# Schematic.net
KiCad netlist of a schematic drawn in EAGLE
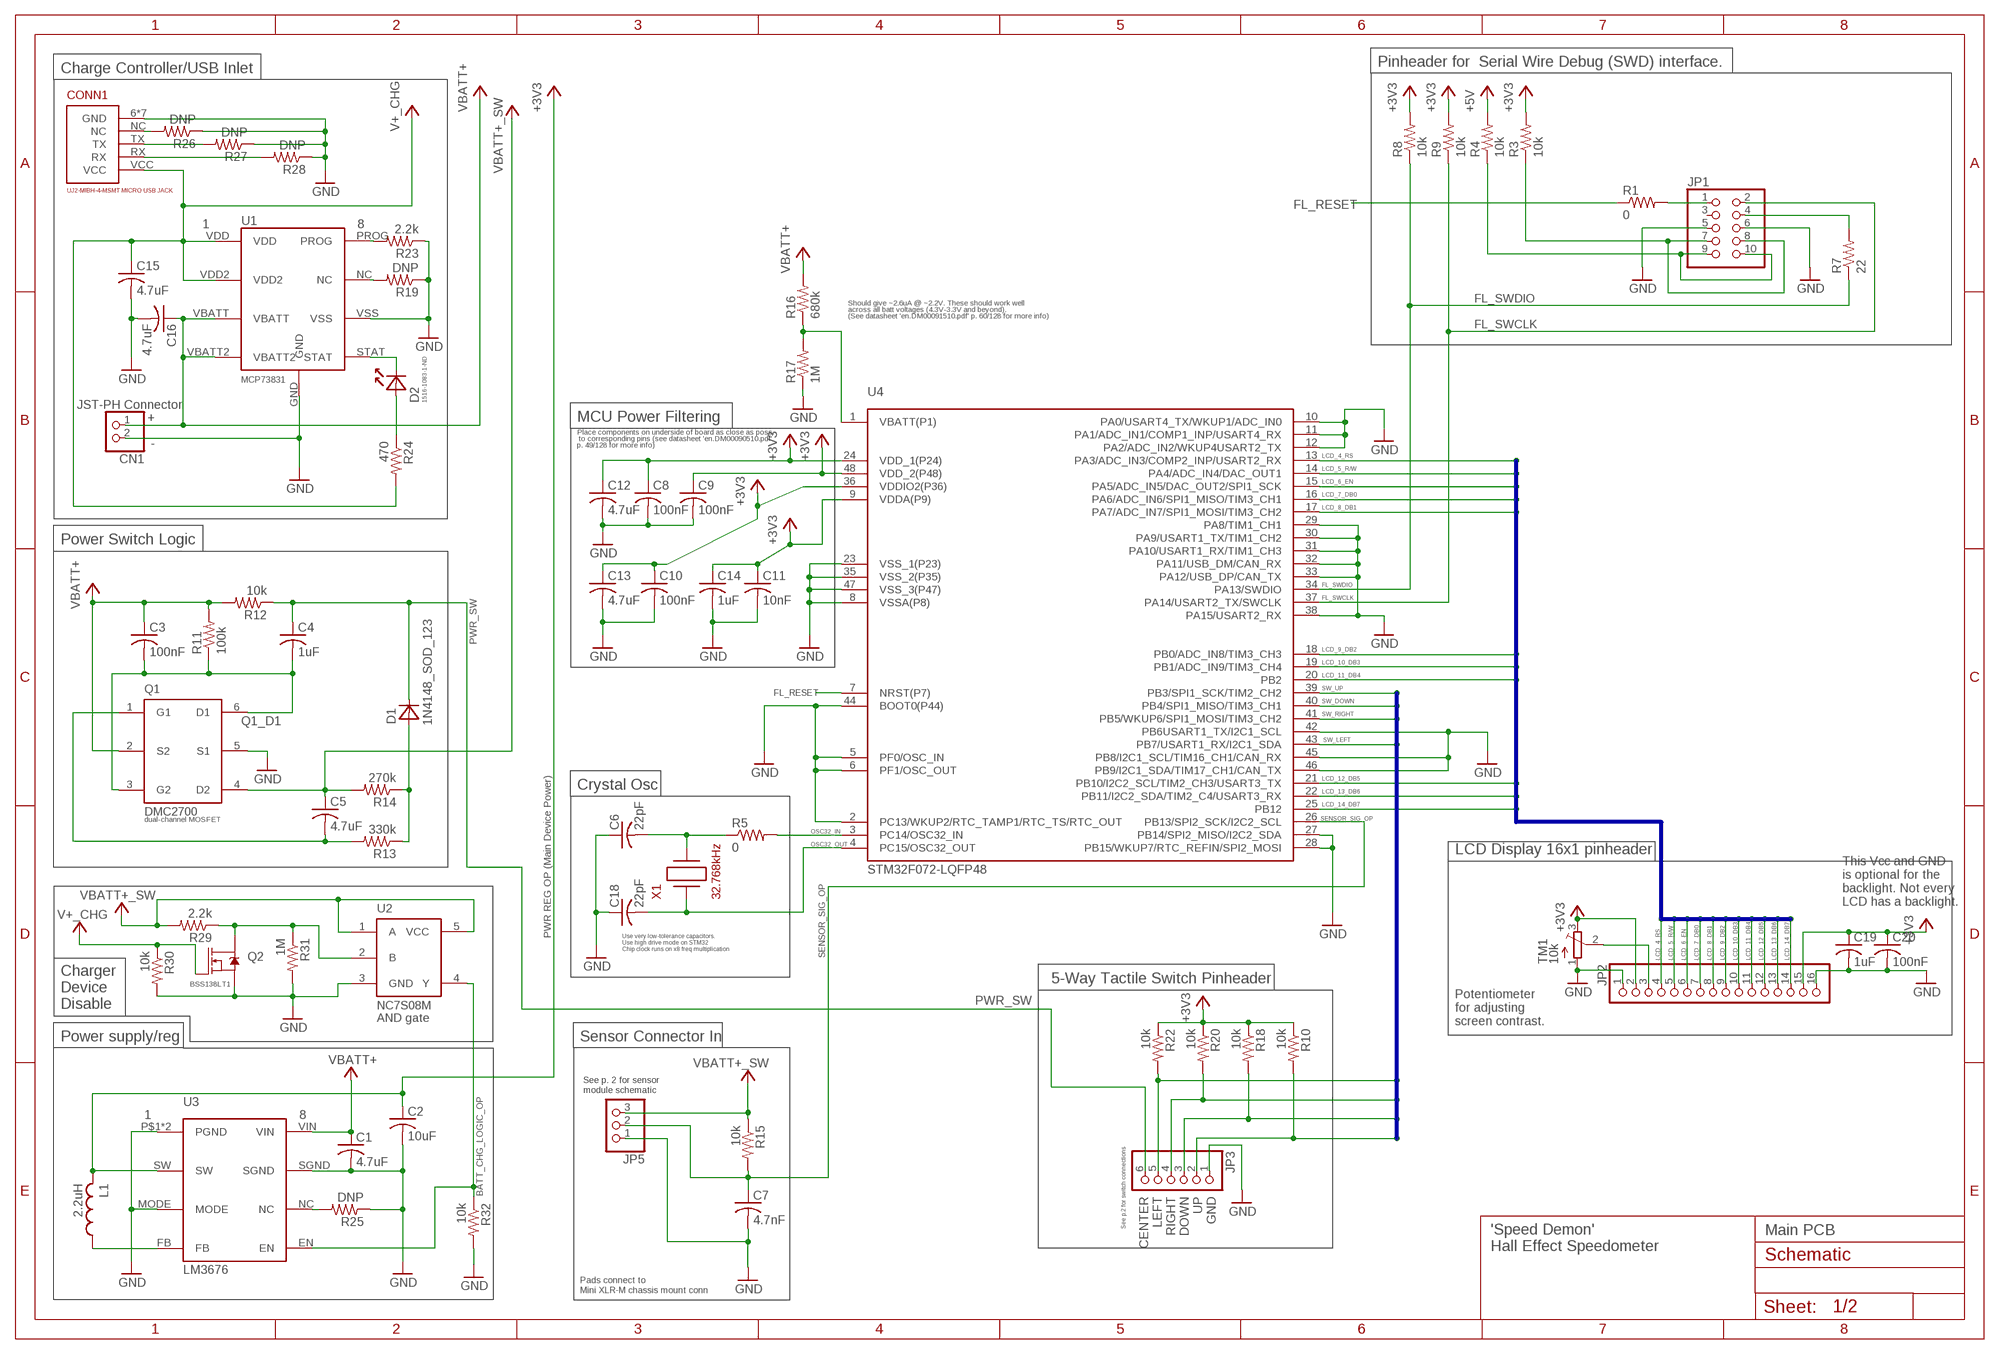
[diagram p0: schematic, sheet 1]
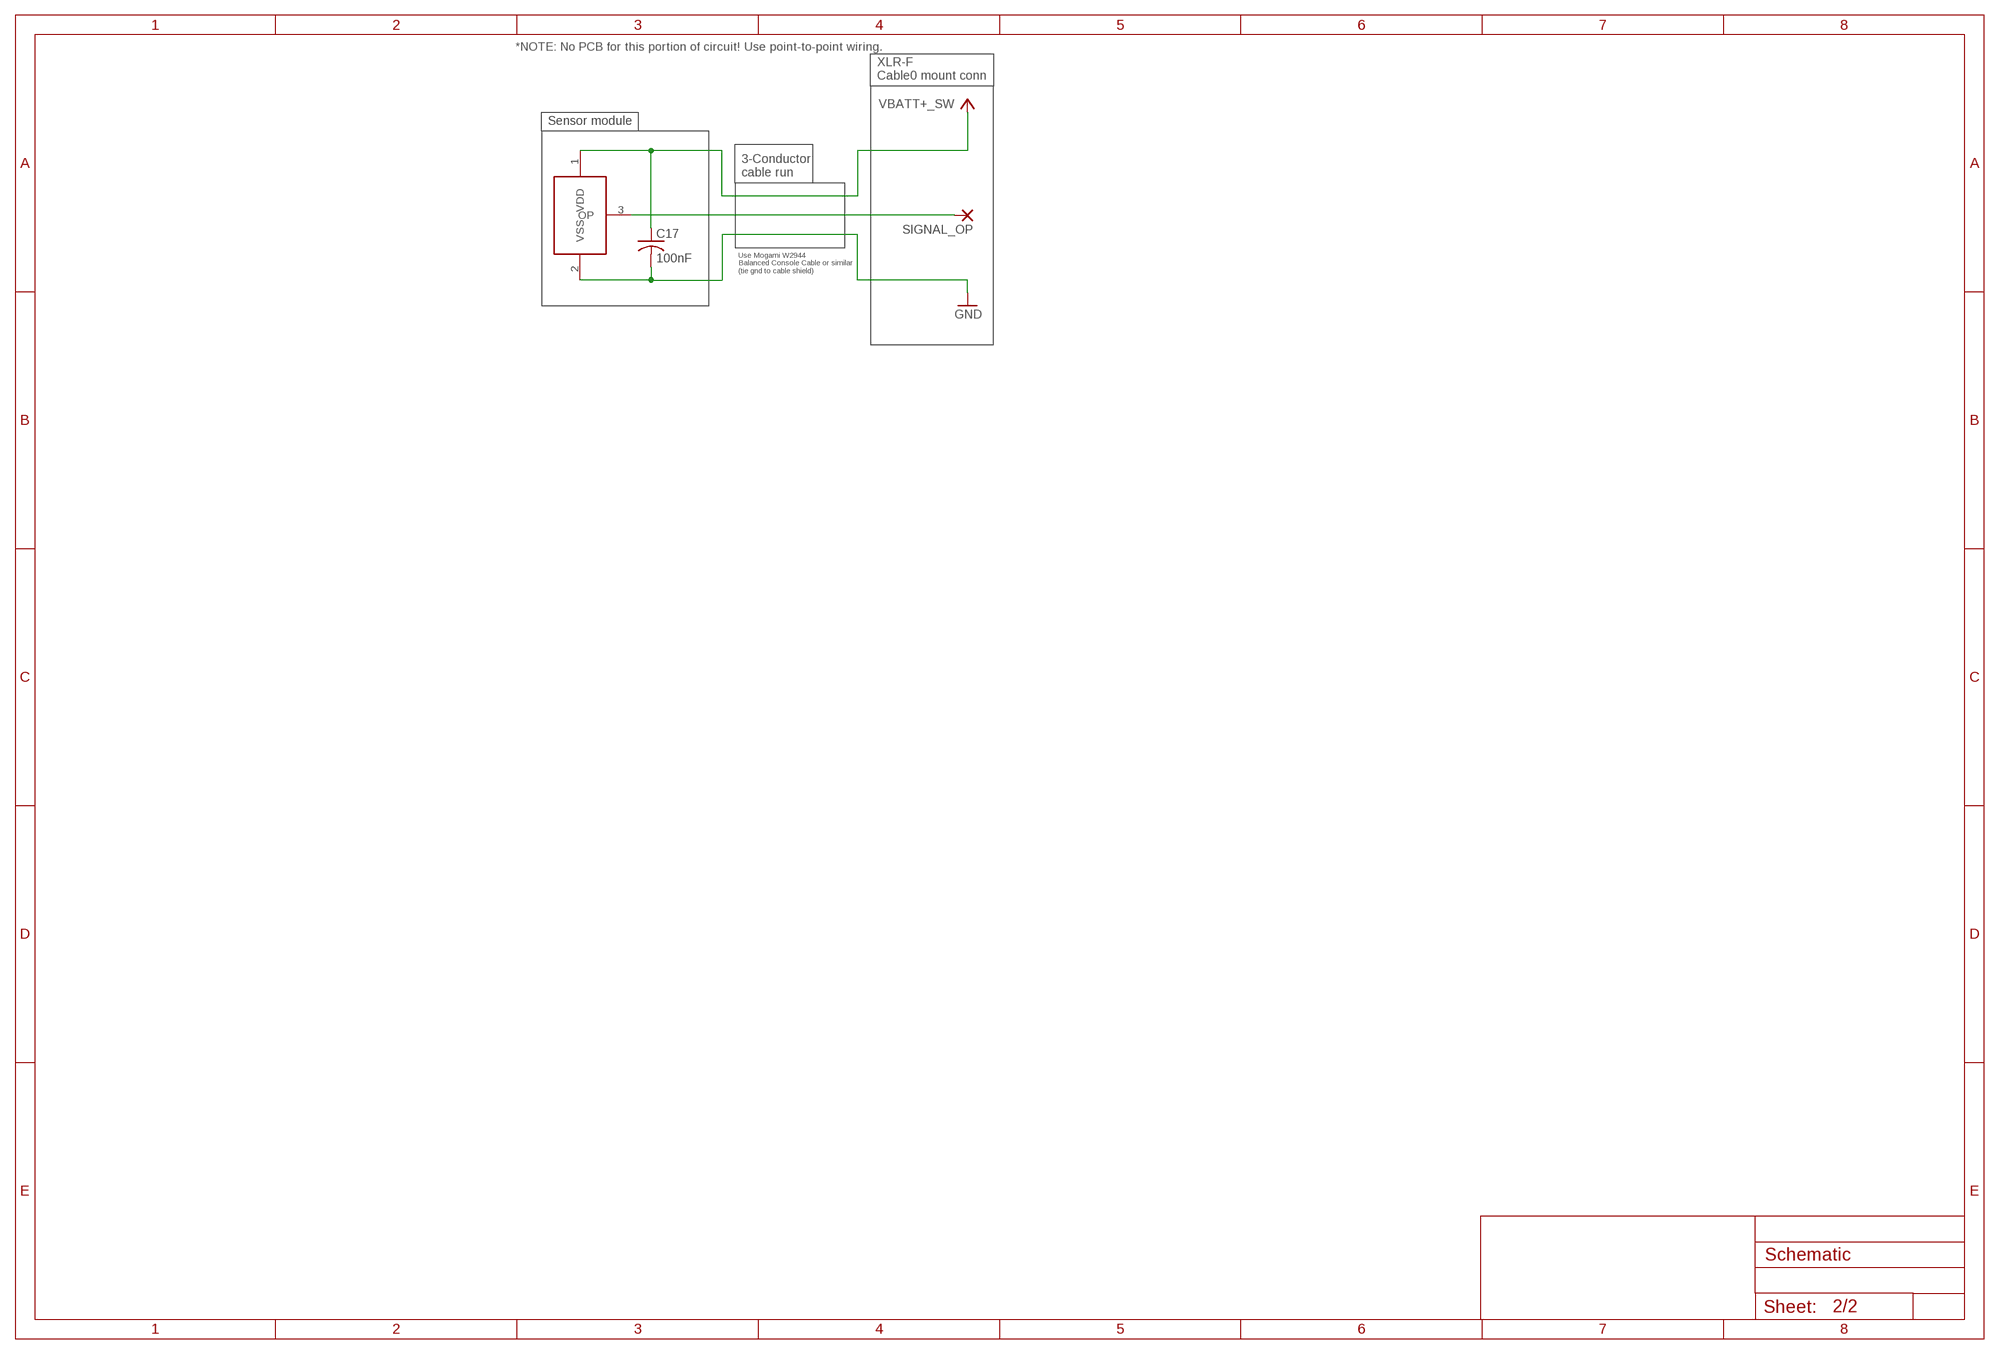
[diagram p1: schematic, sheet 2]

(export (version "E")
  (design (tool "Eeschema 10.0.6"))
  (components
    (comp (ref "C1")
      (value "4.7uF")
      (footprint "eagle-import:C_0805")
      (libsource (lib "eagle-import") (part "C_0805_NP"))
    )
    (comp (ref "C2")
      (value "10uF")
      (footprint "eagle-import:C_0805")
      (libsource (lib "eagle-import") (part "C_0805_NP"))
    )
    (comp (ref "C3")
      (value "100nF")
      (footprint "eagle-import:C_0805")
      (libsource (lib "eagle-import") (part "C_0805_NP"))
    )
    (comp (ref "C4")
      (value "1uF")
      (footprint "eagle-import:C_0805")
      (libsource (lib "eagle-import") (part "C_0805_NP"))
    )
    (comp (ref "C5")
      (value "4.7uF")
      (footprint "eagle-import:C_0805")
      (libsource (lib "eagle-import") (part "C_0805_NP"))
    )
    (comp (ref "C6")
      (value "22pF")
      (footprint "eagle-import:C_0805")
      (libsource (lib "eagle-import") (part "LCRD_SMD_generics_C_0805_NP"))
    )
    (comp (ref "C7")
      (value "4.7nF")
      (footprint "eagle-import:C_0805")
      (libsource (lib "eagle-import") (part "C_0805_NP"))
    )
    (comp (ref "C8")
      (value "100nF")
      (footprint "eagle-import:C_0805")
      (libsource (lib "eagle-import") (part "C_0805_NP"))
    )
    (comp (ref "C9")
      (value "100nF")
      (footprint "eagle-import:C_0805")
      (libsource (lib "eagle-import") (part "C_0805_NP"))
    )
    (comp (ref "C10")
      (value "100nF")
      (footprint "eagle-import:C_0805")
      (libsource (lib "eagle-import") (part "C_0805_NP"))
    )
    (comp (ref "C11")
      (value "10nF")
      (footprint "eagle-import:C_0805")
      (libsource (lib "eagle-import") (part "C_0805_NP"))
    )
    (comp (ref "C12")
      (value "4.7uF")
      (footprint "eagle-import:C_0805")
      (libsource (lib "eagle-import") (part "C_0805_NP"))
    )
    (comp (ref "C13")
      (value "4.7uF")
      (footprint "eagle-import:C_0805")
      (libsource (lib "eagle-import") (part "C_0805_NP"))
    )
    (comp (ref "C14")
      (value "1uF")
      (footprint "eagle-import:C_0805")
      (libsource (lib "eagle-import") (part "C_0805_NP"))
    )
    (comp (ref "C15")
      (value "4.7uF")
      (footprint "eagle-import:C_0805")
      (libsource (lib "eagle-import") (part "C_0805_NP"))
    )
    (comp (ref "C16")
      (value "4.7uF")
      (footprint "eagle-import:C_0805")
      (libsource (lib "eagle-import") (part "C_0805_NP"))
    )
    (comp (ref "C18")
      (value "22pF")
      (footprint "eagle-import:C_0805")
      (libsource (lib "eagle-import") (part "LCRD_SMD_generics_C_0805_NP"))
    )
    (comp (ref "C19")
      (value "1uF")
      (footprint "eagle-import:C_0805")
      (libsource (lib "eagle-import") (part "C_0805_NP"))
    )
    (comp (ref "C20")
      (value "100nF")
      (footprint "eagle-import:C_0805")
      (libsource (lib "eagle-import") (part "C_0805_NP"))
    )
    (comp (ref "CN1")
      (value "JST_2PIN-SMT-RA")
      (footprint "eagle-import:JST-PH-2-SMT-RA")
      (libsource (lib "eagle-import") (part "JST_2PIN-SMT-RA"))
    )
    (comp (ref "CONN1")
      (value "USB-MICRO-B")
      (footprint "eagle-import:UJ2-MIBH-4-MSMT-TR")
      (libsource (lib "eagle-import") (part "USB-MICRO-B"))
    )
    (comp (ref "D1")
      (value "1N4148_SOD_123")
      (footprint "eagle-import:D_SOD_123")
      (libsource (lib "eagle-import") (part "1N4148_SOD_123"))
    )
    (comp (ref "D2")
      (value "LED_0805")
      (footprint "eagle-import:LED_0805")
      (libsource (lib "eagle-import") (part "LED_0805"))
    )
    (comp (ref "JP1")
      (value "PINHD-2X5")
      (footprint "eagle-import:2X05")
      (libsource (lib "eagle-import") (part "PINHD-2X5"))
    )
    (comp (ref "JP2")
      (value "PINHD-1X16")
      (footprint "eagle-import:1X16")
      (libsource (lib "eagle-import") (part "PINHD-1X16"))
    )
    (comp (ref "JP3")
      (value "PINHD-1X6")
      (footprint "eagle-import:1X06")
      (libsource (lib "eagle-import") (part "PINHD-1X6"))
    )
    (comp (ref "JP5")
      (value "PINHD-1X3")
      (footprint "eagle-import:1X03")
      (libsource (lib "eagle-import") (part "PINHD-1X3"))
    )
    (comp (ref "L1")
      (value "2.2uH")
      (footprint "eagle-import:L_0805")
      (libsource (lib "eagle-import") (part "L_0805"))
    )
    (comp (ref "Q1")
      (value "DMC2700")
      (footprint "eagle-import:SOT-23-6")
      (libsource (lib "eagle-import") (part "DMC2700_SOT-23-6"))
    )
    (comp (ref "Q2")
      (value "BSS138LT1_TO-236")
      (footprint "eagle-import:TO-236")
      (libsource (lib "eagle-import") (part "BSS138LT1_TO-236"))
    )
    (comp (ref "R1")
      (value "0")
      (footprint "eagle-import:R0805")
      (libsource (lib "eagle-import") (part "R-US_R0805"))
    )
    (comp (ref "R3")
      (value "10k")
      (footprint "eagle-import:R0805")
      (libsource (lib "eagle-import") (part "R-US_R0805"))
    )
    (comp (ref "R4")
      (value "10k")
      (footprint "eagle-import:R0805")
      (libsource (lib "eagle-import") (part "R-US_R0805"))
    )
    (comp (ref "R5")
      (value "0")
      (footprint "eagle-import:R0805")
      (libsource (lib "eagle-import") (part "R-US_R0805"))
    )
    (comp (ref "R7")
      (value "22")
      (footprint "eagle-import:R0805")
      (libsource (lib "eagle-import") (part "R-US_R0805"))
    )
    (comp (ref "R8")
      (value "10k")
      (footprint "eagle-import:R0805")
      (libsource (lib "eagle-import") (part "R-US_R0805"))
    )
    (comp (ref "R9")
      (value "10k")
      (footprint "eagle-import:R0805")
      (libsource (lib "eagle-import") (part "R-US_R0805"))
    )
    (comp (ref "R10")
      (value "10k")
      (footprint "eagle-import:R_0805")
      (libsource (lib "eagle-import") (part "R_0805"))
    )
    (comp (ref "R11")
      (value "100k")
      (footprint "eagle-import:R_0805")
      (libsource (lib "eagle-import") (part "R_0805"))
    )
    (comp (ref "R12")
      (value "10k")
      (footprint "eagle-import:R_0805")
      (libsource (lib "eagle-import") (part "R_0805"))
    )
    (comp (ref "R13")
      (value "330k")
      (footprint "eagle-import:R_0805")
      (libsource (lib "eagle-import") (part "R_0805"))
    )
    (comp (ref "R14")
      (value "270k")
      (footprint "eagle-import:R_0805")
      (libsource (lib "eagle-import") (part "R_0805"))
    )
    (comp (ref "R15")
      (value "10k")
      (footprint "eagle-import:R_0805")
      (libsource (lib "eagle-import") (part "R_0805"))
    )
    (comp (ref "R16")
      (value "680k")
      (footprint "eagle-import:R_0805")
      (libsource (lib "eagle-import") (part "R_0805"))
    )
    (comp (ref "R17")
      (value "1M")
      (footprint "eagle-import:R_0805")
      (libsource (lib "eagle-import") (part "R_0805"))
    )
    (comp (ref "R18")
      (value "10k")
      (footprint "eagle-import:R_0805")
      (libsource (lib "eagle-import") (part "R_0805"))
    )
    (comp (ref "R19")
      (value "DNP")
      (footprint "eagle-import:R_0805")
      (libsource (lib "eagle-import") (part "R_0805"))
    )
    (comp (ref "R20")
      (value "10k")
      (footprint "eagle-import:R_0805")
      (libsource (lib "eagle-import") (part "R_0805"))
    )
    (comp (ref "R22")
      (value "10k")
      (footprint "eagle-import:R_0805")
      (libsource (lib "eagle-import") (part "R_0805"))
    )
    (comp (ref "R23")
      (value "2.2k")
      (footprint "eagle-import:R_0805")
      (libsource (lib "eagle-import") (part "R_0805"))
    )
    (comp (ref "R24")
      (value "470")
      (footprint "eagle-import:R_0805")
      (libsource (lib "eagle-import") (part "R_0805"))
    )
    (comp (ref "R25")
      (value "DNP")
      (footprint "eagle-import:R_0805")
      (libsource (lib "eagle-import") (part "R_0805"))
    )
    (comp (ref "R26")
      (value "DNP")
      (footprint "eagle-import:R_0805")
      (libsource (lib "eagle-import") (part "R_0805"))
    )
    (comp (ref "R27")
      (value "DNP")
      (footprint "eagle-import:R_0805")
      (libsource (lib "eagle-import") (part "R_0805"))
    )
    (comp (ref "R28")
      (value "DNP")
      (footprint "eagle-import:R_0805")
      (libsource (lib "eagle-import") (part "R_0805"))
    )
    (comp (ref "R29")
      (value "2.2k")
      (footprint "eagle-import:R_0805")
      (libsource (lib "eagle-import") (part "R_0805"))
    )
    (comp (ref "R30")
      (value "10k")
      (footprint "eagle-import:R_0805")
      (libsource (lib "eagle-import") (part "R_0805"))
    )
    (comp (ref "R31")
      (value "1M")
      (footprint "eagle-import:R_0805")
      (libsource (lib "eagle-import") (part "R_0805"))
    )
    (comp (ref "R32")
      (value "10k")
      (footprint "eagle-import:R_0805")
      (libsource (lib "eagle-import") (part "R_0805"))
    )
    (comp (ref "TM1")
      (value "10k")
      (footprint "eagle-import:TRIM-3386")
      (libsource (lib "eagle-import") (part "TRIMPOT3386"))
    )
    (comp (ref "U1")
      (value "MCP73831_8-DFN")
      (footprint "eagle-import:8-DFN-(2X3)")
      (libsource (lib "eagle-import") (part "MCP73831_8-DFN"))
    )
    (comp (ref "U2")
      (value "NC7S08_SOT_23_5")
      (footprint "eagle-import:SOT-23-5")
      (libsource (lib "eagle-import") (part "NC7S08_SOT_23_5"))
    )
    (comp (ref "U3")
      (value "LM3676")
      (footprint "eagle-import:WSON")
      (libsource (lib "eagle-import") (part "LM3676"))
    )
    (comp (ref "U4")
      (value "STM32F072-LQFP48")
      (footprint "eagle-import:LQFP48")
      (libsource (lib "eagle-import") (part "STM32F072-LQFP48"))
    )
    (comp (ref "X1")
      (value "32.768kHz")
      (footprint "eagle-import:CRYSTAL_OSC_3.2X1.5")
      (libsource (lib "eagle-import") (part "XC2292CT-ND"))
    )
    (comp (ref "C17")
      (value "100nF")
      (footprint "eagle-import:C025-024X044")
      (libsource (lib "eagle-import") (part "C-US025-024X044"))
    )
    (comp (ref "SIGNAL_OP")
      (value "1,6/0,8")
      (footprint "eagle-import:1,6_0,8")
      (libsource (lib "eagle-import") (part "1,6/0,8"))
    )
    (comp (ref "U1A")
      (value "US5881")
      (footprint "eagle-import:TO-92")
      (libsource (lib "eagle-import") (part "US5881"))
    )
  )
  (nets
    (net (code "1") (name "+3V3") (class "Default")
      (node (ref "C10") (pin "1") (pinfunction "1_1") (pintype "passive"))
      (node (ref "C11") (pin "1") (pinfunction "1_1") (pintype "passive"))
      (node (ref "C12") (pin "1") (pinfunction "1_1") (pintype "passive"))
      (node (ref "C13") (pin "1") (pinfunction "1_1") (pintype "passive"))
      (node (ref "C14") (pin "1") (pinfunction "1_1") (pintype "passive"))
      (node (ref "C19") (pin "1") (pinfunction "1_1") (pintype "passive"))
      (node (ref "C2") (pin "1") (pinfunction "1_1") (pintype "passive"))
      (node (ref "C20") (pin "1") (pinfunction "1_1") (pintype "passive"))
      (node (ref "C8") (pin "1") (pinfunction "1_1") (pintype "passive"))
      (node (ref "C9") (pin "1") (pinfunction "1_1") (pintype "passive"))
      (node (ref "JP2") (pin "15") (pinfunction "15_15") (pintype "passive"))
      (node (ref "JP2") (pin "2") (pinfunction "2_2") (pintype "passive"))
      (node (ref "L1") (pin "2") (pinfunction "2_2") (pintype "passive"))
      (node (ref "R10") (pin "1") (pinfunction "1_1") (pintype "passive"))
      (node (ref "R18") (pin "1") (pinfunction "1_1") (pintype "passive"))
      (node (ref "R20") (pin "1") (pinfunction "1_1") (pintype "passive"))
      (node (ref "R22") (pin "1") (pinfunction "1_1") (pintype "passive"))
      (node (ref "R3") (pin "2") (pinfunction "2_2") (pintype "passive"))
      (node (ref "R8") (pin "2") (pinfunction "2_2") (pintype "passive"))
      (node (ref "R9") (pin "2") (pinfunction "2_2") (pintype "passive"))
      (node (ref "TM1") (pin "3") (pinfunction "E_3") (pintype "passive"))
      (node (ref "U3") (pin "SW") (pinfunction "SW_SW") (pintype "bidirectional"))
      (node (ref "U4") (pin "24") (pinfunction "VDD_1(P24)_24") (pintype "bidirectional"))
      (node (ref "U4") (pin "36") (pinfunction "VDDIO2(P36)_36") (pintype "bidirectional"))
      (node (ref "U4") (pin "48") (pinfunction "VDD_2(P48)_48") (pintype "bidirectional"))
      (node (ref "U4") (pin "9") (pinfunction "VDDA(P9)_9") (pintype "bidirectional"))
    )
    (net (code "2") (name "+5V") (class "Default")
      (node (ref "R4") (pin "2") (pinfunction "2_2") (pintype "passive"))
    )
    (net (code "3") (name "+V+_CHG") (class "Default")
      (node (ref "C15") (pin "1") (pinfunction "1_1") (pintype "passive"))
      (node (ref "CONN1") (pin "VCC") (pinfunction "VCC_VCC") (pintype "bidirectional"))
      (node (ref "Q2") (pin "1") (pinfunction "G_1") (pintype "bidirectional"))
      (node (ref "R24") (pin "2") (pinfunction "2_2") (pintype "passive"))
      (node (ref "R30") (pin "1") (pinfunction "1_1") (pintype "passive"))
      (node (ref "U1") (pin "VDD") (pinfunction "VDD_VDD") (pintype "power_in"))
      (node (ref "U1") (pin "VDD2") (pinfunction "VDD2_VDD2") (pintype "bidirectional"))
    )
    (net (code "4") (name "BATT_CHG_LOGIC_OP") (class "Default")
      (node (ref "R32") (pin "1") (pinfunction "1_1") (pintype "passive"))
      (node (ref "U2") (pin "4") (pinfunction "Y_4") (pintype "bidirectional"))
      (node (ref "U3") (pin "EN") (pinfunction "EN_EN") (pintype "bidirectional"))
    )
    (net (code "5") (name "FL_RESET") (class "Default")
      (node (ref "R1") (pin "1") (pinfunction "1_1") (pintype "passive"))
      (node (ref "U4") (pin "7") (pinfunction "NRST(P7)_7") (pintype "bidirectional"))
    )
    (net (code "6") (name "FL_SWCLK") (class "Default")
      (node (ref "JP1") (pin "2") (pinfunction "2_2") (pintype "passive"))
      (node (ref "R9") (pin "1") (pinfunction "1_1") (pintype "passive"))
      (node (ref "U4") (pin "37") (pinfunction "PA14/USART2_TX/SWCLK_37") (pintype "bidirectional"))
    )
    (net (code "7") (name "FL_SWDIO") (class "Default")
      (node (ref "R7") (pin "1") (pinfunction "1_1") (pintype "passive"))
      (node (ref "R8") (pin "1") (pinfunction "1_1") (pintype "passive"))
      (node (ref "U4") (pin "34") (pinfunction "PA13/SWDIO_34") (pintype "bidirectional"))
    )
    (net (code "8") (name "GND") (class "Default")
      (node (ref "C1") (pin "2") (pinfunction "2_2") (pintype "passive"))
      (node (ref "C10") (pin "2") (pinfunction "2_2") (pintype "passive"))
      (node (ref "C11") (pin "2") (pinfunction "2_2") (pintype "passive"))
      (node (ref "C12") (pin "2") (pinfunction "2_2") (pintype "passive"))
      (node (ref "C13") (pin "2") (pinfunction "2_2") (pintype "passive"))
      (node (ref "C14") (pin "2") (pinfunction "2_2") (pintype "passive"))
      (node (ref "C15") (pin "2") (pinfunction "2_2") (pintype "passive"))
      (node (ref "C16") (pin "2") (pinfunction "2_2") (pintype "passive"))
      (node (ref "C17") (pin "2") (pinfunction "2_2") (pintype "passive"))
      (node (ref "C18") (pin "1") (pinfunction "1_1") (pintype "passive"))
      (node (ref "C19") (pin "2") (pinfunction "2_2") (pintype "passive"))
      (node (ref "C2") (pin "2") (pinfunction "2_2") (pintype "passive"))
      (node (ref "C20") (pin "2") (pinfunction "2_2") (pintype "passive"))
      (node (ref "C6") (pin "1") (pinfunction "1_1") (pintype "passive"))
      (node (ref "C7") (pin "2") (pinfunction "2_2") (pintype "passive"))
      (node (ref "C8") (pin "2") (pinfunction "2_2") (pintype "passive"))
      (node (ref "C9") (pin "2") (pinfunction "2_2") (pintype "passive"))
      (node (ref "CN1") (pin "2") (pinfunction "1_2") (pintype "passive"))
      (node (ref "CONN1") (pin "10") (pinfunction "GND_10") (pintype "bidirectional"))
      (node (ref "CONN1") (pin "11") (pinfunction "GND_11") (pintype "bidirectional"))
      (node (ref "CONN1") (pin "6") (pinfunction "GND_6") (pintype "bidirectional"))
      (node (ref "CONN1") (pin "7") (pinfunction "GND_7") (pintype "bidirectional"))
      (node (ref "CONN1") (pin "8") (pinfunction "GND_8") (pintype "bidirectional"))
      (node (ref "CONN1") (pin "9") (pinfunction "GND_9") (pintype "bidirectional"))
      (node (ref "CONN1") (pin "GND") (pinfunction "GND_GND") (pintype "bidirectional"))
      (node (ref "JP1") (pin "5") (pinfunction "5_5") (pintype "passive"))
      (node (ref "JP1") (pin "6") (pinfunction "6_6") (pintype "passive"))
      (node (ref "JP2") (pin "1") (pinfunction "1_1") (pintype "passive"))
      (node (ref "JP2") (pin "16") (pinfunction "16_16") (pintype "passive"))
      (node (ref "JP3") (pin "1") (pinfunction "1_1") (pintype "passive"))
      (node (ref "JP5") (pin "1") (pinfunction "1_1") (pintype "passive"))
      (node (ref "Q1") (pin "5") (pinfunction "S1_5") (pintype "bidirectional"))
      (node (ref "Q2") (pin "2") (pinfunction "S_2") (pintype "bidirectional"))
      (node (ref "R17") (pin "1") (pinfunction "1_1") (pintype "passive"))
      (node (ref "R19") (pin "1") (pinfunction "1_1") (pintype "passive"))
      (node (ref "R23") (pin "1") (pinfunction "1_1") (pintype "passive"))
      (node (ref "R25") (pin "1") (pinfunction "1_1") (pintype "passive"))
      (node (ref "R26") (pin "1") (pinfunction "1_1") (pintype "passive"))
      (node (ref "R27") (pin "1") (pinfunction "1_1") (pintype "passive"))
      (node (ref "R28") (pin "1") (pinfunction "1_1") (pintype "passive"))
      (node (ref "R30") (pin "2") (pinfunction "2_2") (pintype "passive"))
      (node (ref "R31") (pin "2") (pinfunction "2_2") (pintype "passive"))
      (node (ref "R32") (pin "2") (pinfunction "2_2") (pintype "passive"))
      (node (ref "TM1") (pin "1") (pinfunction "A_1") (pintype "passive"))
      (node (ref "U1") (pin "GND") (pinfunction "GND_GND") (pintype "bidirectional"))
      (node (ref "U1") (pin "VSS") (pinfunction "VSS_VSS") (pintype "bidirectional"))
      (node (ref "U1A") (pin "2") (pinfunction "VSS_2") (pintype "bidirectional"))
      (node (ref "U2") (pin "3") (pinfunction "GND_3") (pintype "bidirectional"))
      (node (ref "U3") (pin "MODE") (pinfunction "MODE_MODE") (pintype "bidirectional"))
      (node (ref "U3") (pin "P$1") (pinfunction "PGND_P$1") (pintype "power_in"))
      (node (ref "U3") (pin "PGND") (pinfunction "PGND_PGND") (pintype "power_in"))
      (node (ref "U3") (pin "SGND") (pinfunction "SGND_SGND") (pintype "power_in"))
      (node (ref "U4") (pin "10") (pinfunction "PA0/USART4_TX/WKUP1/ADC_IN0_10") (pintype "bidirectional"))
      (node (ref "U4") (pin "11") (pinfunction "PA1/ADC_IN1/COMP1_INP/USART4_RX_11") (pintype "bidirectional"))
      (node (ref "U4") (pin "12") (pinfunction "PA2/ADC_IN2/WKUP4USART2_TX_12") (pintype "bidirectional"))
      (node (ref "U4") (pin "2") (pinfunction "PC13/WKUP2/RTC_TAMP1/RTC_TS/RTC_OUT_2") (pintype "bidirectional"))
      (node (ref "U4") (pin "23") (pinfunction "VSS_1(P23)_23") (pintype "bidirectional"))
      (node (ref "U4") (pin "27") (pinfunction "PB14/SPI2_MISO/I2C2_SDA_27") (pintype "bidirectional"))
      (node (ref "U4") (pin "28") (pinfunction "PB15/WKUP7/RTC_REFIN/SPI2_MOSI_28") (pintype "bidirectional"))
      (node (ref "U4") (pin "29") (pinfunction "PA8/TIM1_CH1_29") (pintype "bidirectional"))
      (node (ref "U4") (pin "30") (pinfunction "PA9/USART1_TX/TIM1_CH2_30") (pintype "bidirectional"))
      (node (ref "U4") (pin "31") (pinfunction "PA10/USART1_RX/TIM1_CH3_31") (pintype "bidirectional"))
      (node (ref "U4") (pin "32") (pinfunction "PA11/USB_DM/CAN_RX_32") (pintype "bidirectional"))
      (node (ref "U4") (pin "33") (pinfunction "PA12/USB_DP/CAN_TX_33") (pintype "bidirectional"))
      (node (ref "U4") (pin "35") (pinfunction "VSS_2(P35)_35") (pintype "bidirectional"))
      (node (ref "U4") (pin "38") (pinfunction "PA15/USART2_RX_38") (pintype "bidirectional"))
      (node (ref "U4") (pin "42") (pinfunction "PB6USART1_TX/I2C1_SCL_42") (pintype "bidirectional"))
      (node (ref "U4") (pin "44") (pinfunction "BOOT0(P44)_44") (pintype "bidirectional"))
      (node (ref "U4") (pin "45") (pinfunction "PB8/I2C1_SCL/TIM16_CH1/CAN_RX_45") (pintype "bidirectional"))
      (node (ref "U4") (pin "46") (pinfunction "PB9/I2C1_SDA/TIM17_CH1/CAN_TX_46") (pintype "bidirectional"))
      (node (ref "U4") (pin "47") (pinfunction "VSS_3(P47)_47") (pintype "bidirectional"))
      (node (ref "U4") (pin "5") (pinfunction "PF0/OSC_IN_5") (pintype "bidirectional"))
      (node (ref "U4") (pin "6") (pinfunction "PF1/OSC_OUT_6") (pintype "bidirectional"))
      (node (ref "U4") (pin "8") (pinfunction "VSSA(P8)_8") (pintype "bidirectional"))
    )
    (net (code "9") (name "LCD_4_RS") (class "Default")
      (node (ref "JP2") (pin "4") (pinfunction "4_4") (pintype "passive"))
      (node (ref "U4") (pin "13") (pinfunction "PA3/ADC_IN3/COMP2_INP/USART2_RX_13") (pintype "bidirectional"))
    )
    (net (code "10") (name "LCD_5_R{slash}W") (class "Default")
      (node (ref "JP2") (pin "5") (pinfunction "5_5") (pintype "passive"))
      (node (ref "U4") (pin "14") (pinfunction "PA4/ADC_IN4/DAC_OUT1_14") (pintype "bidirectional"))
    )
    (net (code "11") (name "LCD_6_EN") (class "Default")
      (node (ref "JP2") (pin "6") (pinfunction "6_6") (pintype "passive"))
      (node (ref "U4") (pin "15") (pinfunction "PA5/ADC_IN5/DAC_OUT2/SPI1_SCK_15") (pintype "bidirectional"))
    )
    (net (code "12") (name "LCD_7_DB0") (class "Default")
      (node (ref "JP2") (pin "7") (pinfunction "7_7") (pintype "passive"))
      (node (ref "U4") (pin "16") (pinfunction "PA6/ADC_IN6/SPI1_MISO/TIM3_CH1_16") (pintype "bidirectional"))
    )
    (net (code "13") (name "LCD_8_DB1") (class "Default")
      (node (ref "JP2") (pin "8") (pinfunction "8_8") (pintype "passive"))
      (node (ref "U4") (pin "17") (pinfunction "PA7/ADC_IN7/SPI1_MOSI/TIM3_CH2_17") (pintype "bidirectional"))
    )
    (net (code "14") (name "LCD_9_DB2") (class "Default")
      (node (ref "JP2") (pin "9") (pinfunction "9_9") (pintype "passive"))
      (node (ref "U4") (pin "18") (pinfunction "PB0/ADC_IN8/TIM3_CH3_18") (pintype "bidirectional"))
    )
    (net (code "15") (name "LCD_10_DB3") (class "Default")
      (node (ref "JP2") (pin "10") (pinfunction "10_10") (pintype "passive"))
      (node (ref "U4") (pin "19") (pinfunction "PB1/ADC_IN9/TIM3_CH4_19") (pintype "bidirectional"))
    )
    (net (code "16") (name "LCD_11_DB4") (class "Default")
      (node (ref "JP2") (pin "11") (pinfunction "11_11") (pintype "passive"))
      (node (ref "U4") (pin "20") (pinfunction "PB2_20") (pintype "bidirectional"))
    )
    (net (code "17") (name "LCD_12_DB5") (class "Default")
      (node (ref "JP2") (pin "12") (pinfunction "12_12") (pintype "passive"))
      (node (ref "U4") (pin "21") (pinfunction "PB10/I2C2_SCL/TIM2_CH3/USART3_TX_21") (pintype "bidirectional"))
    )
    (net (code "18") (name "LCD_13_DB6") (class "Default")
      (node (ref "JP2") (pin "13") (pinfunction "13_13") (pintype "passive"))
      (node (ref "U4") (pin "22") (pinfunction "PB11/I2C2_SDA/TIM2_C4/USART3_RX_22") (pintype "bidirectional"))
    )
    (net (code "19") (name "LCD_14_DB7") (class "Default")
      (node (ref "JP2") (pin "14") (pinfunction "14_14") (pintype "passive"))
      (node (ref "U4") (pin "25") (pinfunction "PB12_25") (pintype "bidirectional"))
    )
    (net (code "20") (name "Net-(CONN1-PadNC)") (class "Default")
      (node (ref "CONN1") (pin "NC") (pinfunction "NC_NC") (pintype "bidirectional"))
      (node (ref "R26") (pin "2") (pinfunction "2_2") (pintype "passive"))
    )
    (net (code "21") (name "Net-(CONN1-PadRX)") (class "Default")
      (node (ref "CONN1") (pin "RX") (pinfunction "RX_RX") (pintype "bidirectional"))
      (node (ref "R28") (pin "2") (pinfunction "2_2") (pintype "passive"))
    )
    (net (code "22") (name "Net-(CONN1-PadTX)") (class "Default")
      (node (ref "CONN1") (pin "TX") (pinfunction "TX_TX") (pintype "bidirectional"))
      (node (ref "R27") (pin "2") (pinfunction "2_2") (pintype "passive"))
    )
    (net (code "23") (name "Net-(D1-A)") (class "Default")
      (node (ref "D1") (pin "1") (pinfunction "A_1") (pintype "passive"))
      (node (ref "R13") (pin "1") (pinfunction "1_1") (pintype "passive"))
      (node (ref "R14") (pin "1") (pinfunction "1_1") (pintype "passive"))
    )
    (net (code "24") (name "Net-(D2-A)") (class "Default")
      (node (ref "D2") (pin "1") (pinfunction "A_1") (pintype "passive"))
      (node (ref "R24") (pin "1") (pinfunction "1_1") (pintype "passive"))
    )
    (net (code "25") (name "Net-(D2-C)") (class "Default")
      (node (ref "D2") (pin "2") (pinfunction "C_2") (pintype "passive"))
      (node (ref "U1") (pin "STAT") (pinfunction "STAT_STAT") (pintype "bidirectional"))
    )
    (net (code "26") (name "Net-(JP1-Pad1)") (class "Default")
      (node (ref "JP1") (pin "1") (pinfunction "1_1") (pintype "passive"))
      (node (ref "R1") (pin "2") (pinfunction "2_2") (pintype "passive"))
    )
    (net (code "27") (name "Net-(JP1-Pad4)") (class "Default")
      (node (ref "JP1") (pin "4") (pinfunction "4_4") (pintype "passive"))
      (node (ref "R7") (pin "2") (pinfunction "2_2") (pintype "passive"))
    )
    (net (code "28") (name "Net-(JP1-Pad7)") (class "Default")
      (node (ref "JP1") (pin "7") (pinfunction "7_7") (pintype "passive"))
      (node (ref "JP1") (pin "8") (pinfunction "8_8") (pintype "passive"))
      (node (ref "R3") (pin "1") (pinfunction "1_1") (pintype "passive"))
    )
    (net (code "29") (name "Net-(JP1-Pad10)") (class "Default")
      (node (ref "JP1") (pin "10") (pinfunction "10_10") (pintype "passive"))
      (node (ref "JP1") (pin "9") (pinfunction "9_9") (pintype "passive"))
      (node (ref "R4") (pin "1") (pinfunction "1_1") (pintype "passive"))
    )
    (net (code "30") (name "Net-(L1-Pad1)") (class "Default")
      (node (ref "L1") (pin "1") (pinfunction "1_1") (pintype "passive"))
      (node (ref "U3") (pin "FB") (pinfunction "FB_FB") (pintype "bidirectional"))
    )
    (net (code "31") (name "Net-(Q1-G1)") (class "Default")
      (node (ref "C5") (pin "2") (pinfunction "2_2") (pintype "passive"))
      (node (ref "Q1") (pin "1") (pinfunction "G1_1") (pintype "bidirectional"))
      (node (ref "R13") (pin "2") (pinfunction "2_2") (pintype "passive"))
    )
    (net (code "32") (name "Net-(Q2-D)") (class "Default")
      (node (ref "Q2") (pin "3") (pinfunction "D_3") (pintype "bidirectional"))
      (node (ref "R29") (pin "1") (pinfunction "1_1") (pintype "passive"))
      (node (ref "R31") (pin "1") (pinfunction "1_1") (pintype "passive"))
      (node (ref "U2") (pin "2") (pinfunction "B_2") (pintype "bidirectional"))
    )
    (net (code "33") (name "Net-(R19-Pad2)") (class "Default")
      (node (ref "R19") (pin "2") (pinfunction "2_2") (pintype "passive"))
      (node (ref "U1") (pin "NC") (pinfunction "NC_NC") (pintype "power_in"))
    )
    (net (code "34") (name "Net-(R23-Pad2)") (class "Default")
      (node (ref "R23") (pin "2") (pinfunction "2_2") (pintype "passive"))
      (node (ref "U1") (pin "PROG") (pinfunction "PROG_PROG") (pintype "bidirectional"))
    )
    (net (code "35") (name "Net-(R25-Pad2)") (class "Default")
      (node (ref "R25") (pin "2") (pinfunction "2_2") (pintype "passive"))
      (node (ref "U3") (pin "NC") (pinfunction "NC_NC") (pintype "bidirectional"))
    )
    (net (code "36") (name "Net-(SIGNAL_OP-P)") (class "Default")
      (node (ref "SIGNAL_OP") (pin "1") (pinfunction "P_1") (pintype "passive"))
      (node (ref "U1A") (pin "3") (pinfunction "OP_3") (pintype "bidirectional"))
    )
    (net (code "37") (name "Net-(TM1-S)") (class "Default")
      (node (ref "JP2") (pin "3") (pinfunction "3_3") (pintype "passive"))
      (node (ref "TM1") (pin "2") (pinfunction "S_2") (pintype "passive"))
    )
    (net (code "38") (name "Net-(U4-PC14{slash}OSC32_IN)") (class "Default")
      (node (ref "R5") (pin "2") (pinfunction "2_2") (pintype "passive"))
      (node (ref "U4") (pin "3") (pinfunction "PC14/OSC32_IN_3") (pintype "bidirectional"))
    )
    (net (code "39") (name "Net-(U4-VBATT(P1))") (class "Default")
      (node (ref "R16") (pin "1") (pinfunction "1_1") (pintype "passive"))
      (node (ref "R17") (pin "2") (pinfunction "2_2") (pintype "passive"))
      (node (ref "U4") (pin "1") (pinfunction "VBATT(P1)_1") (pintype "bidirectional"))
    )
    (net (code "40") (name "OSC32_IN") (class "Default")
      (node (ref "C6") (pin "2") (pinfunction "2_2") (pintype "passive"))
      (node (ref "R5") (pin "1") (pinfunction "1_1") (pintype "passive"))
      (node (ref "X1") (pin "P$1") (pinfunction "1_P$1") (pintype "bidirectional"))
    )
    (net (code "41") (name "OSC32_OUT") (class "Default")
      (node (ref "C18") (pin "2") (pinfunction "2_2") (pintype "passive"))
      (node (ref "U4") (pin "4") (pinfunction "PC15/OSC32_OUT_4") (pintype "bidirectional"))
      (node (ref "X1") (pin "P$2") (pinfunction "2_P$2") (pintype "bidirectional"))
    )
    (net (code "42") (name "PWR_SW") (class "Default")
      (node (ref "C4") (pin "1") (pinfunction "1_1") (pintype "passive"))
      (node (ref "D1") (pin "2") (pinfunction "C_2") (pintype "passive"))
      (node (ref "JP3") (pin "6") (pinfunction "6_6") (pintype "passive"))
      (node (ref "R12") (pin "1") (pinfunction "1_1") (pintype "passive"))
    )
    (net (code "43") (name "Q1_D1") (class "Default")
      (node (ref "C3") (pin "2") (pinfunction "2_2") (pintype "passive"))
      (node (ref "C4") (pin "2") (pinfunction "2_2") (pintype "passive"))
      (node (ref "Q1") (pin "3") (pinfunction "G2_3") (pintype "bidirectional"))
      (node (ref "Q1") (pin "6") (pinfunction "D1_6") (pintype "bidirectional"))
      (node (ref "R11") (pin "1") (pinfunction "1_1") (pintype "passive"))
    )
    (net (code "44") (name "SENSOR_SIG_OP") (class "Default")
      (node (ref "C7") (pin "1") (pinfunction "1_1") (pintype "passive"))
      (node (ref "JP5") (pin "2") (pinfunction "2_2") (pintype "passive"))
      (node (ref "R15") (pin "2") (pinfunction "2_2") (pintype "passive"))
      (node (ref "U4") (pin "26") (pinfunction "PB13/SPI2_SCK/I2C2_SCL_26") (pintype "bidirectional"))
    )
    (net (code "45") (name "SW_DOWN") (class "Default")
      (node (ref "JP3") (pin "3") (pinfunction "3_3") (pintype "passive"))
      (node (ref "R18") (pin "2") (pinfunction "2_2") (pintype "passive"))
      (node (ref "U4") (pin "40") (pinfunction "PB4/SPI1_MISO/TIM3_CH1_40") (pintype "bidirectional"))
    )
    (net (code "46") (name "SW_LEFT") (class "Default")
      (node (ref "JP3") (pin "5") (pinfunction "5_5") (pintype "passive"))
      (node (ref "R22") (pin "2") (pinfunction "2_2") (pintype "passive"))
      (node (ref "U4") (pin "43") (pinfunction "PB7/USART1_RX/I2C1_SDA_43") (pintype "bidirectional"))
    )
    (net (code "47") (name "SW_RIGHT") (class "Default")
      (node (ref "JP3") (pin "4") (pinfunction "4_4") (pintype "passive"))
      (node (ref "R20") (pin "2") (pinfunction "2_2") (pintype "passive"))
      (node (ref "U4") (pin "41") (pinfunction "PB5/WKUP6/SPI1_MOSI/TIM3_CH2_41") (pintype "bidirectional"))
    )
    (net (code "48") (name "SW_UP") (class "Default")
      (node (ref "JP3") (pin "2") (pinfunction "2_2") (pintype "passive"))
      (node (ref "R10") (pin "2") (pinfunction "2_2") (pintype "passive"))
      (node (ref "U4") (pin "39") (pinfunction "PB3/SPI1_SCK/TIM2_CH2_39") (pintype "bidirectional"))
    )
    (net (code "49") (name "VBATT+") (class "Default")
      (node (ref "C1") (pin "1") (pinfunction "1_1") (pintype "passive"))
      (node (ref "C16") (pin "1") (pinfunction "1_1") (pintype "passive"))
      (node (ref "C3") (pin "1") (pinfunction "1_1") (pintype "passive"))
      (node (ref "CN1") (pin "1") (pinfunction "2_1") (pintype "passive"))
      (node (ref "Q1") (pin "2") (pinfunction "S2_2") (pintype "bidirectional"))
      (node (ref "R11") (pin "2") (pinfunction "2_2") (pintype "passive"))
      (node (ref "R12") (pin "2") (pinfunction "2_2") (pintype "passive"))
      (node (ref "R16") (pin "2") (pinfunction "2_2") (pintype "passive"))
      (node (ref "U1") (pin "VBATT") (pinfunction "VBATT_VBATT") (pintype "bidirectional"))
      (node (ref "U1") (pin "VBATT2") (pinfunction "VBATT2_VBATT2") (pintype "bidirectional"))
      (node (ref "U3") (pin "VIN") (pinfunction "VIN_VIN") (pintype "bidirectional"))
    )
    (net (code "50") (name "VBATT+_SW") (class "Default")
      (node (ref "C17") (pin "1") (pinfunction "1_1") (pintype "passive"))
      (node (ref "C5") (pin "1") (pinfunction "1_1") (pintype "passive"))
      (node (ref "JP5") (pin "3") (pinfunction "3_3") (pintype "passive"))
      (node (ref "Q1") (pin "4") (pinfunction "D2_4") (pintype "bidirectional"))
      (node (ref "R14") (pin "2") (pinfunction "2_2") (pintype "passive"))
      (node (ref "R15") (pin "1") (pinfunction "1_1") (pintype "passive"))
      (node (ref "R29") (pin "2") (pinfunction "2_2") (pintype "passive"))
      (node (ref "U1A") (pin "1") (pinfunction "VDD_1") (pintype "bidirectional"))
      (node (ref "U2") (pin "1") (pinfunction "A_1") (pintype "bidirectional"))
      (node (ref "U2") (pin "5") (pinfunction "VCC_5") (pintype "bidirectional"))
    )
    (net (code "51") (name "unconnected-(JP1-Pad3)") (class "Default")
      (node (ref "JP1") (pin "3") (pinfunction "3_3") (pintype "passive"))
    )
  )
)
